# smoothieboard_daugterboard_Plasma.net
KiCad netlist of a schematic drawn in EAGLE
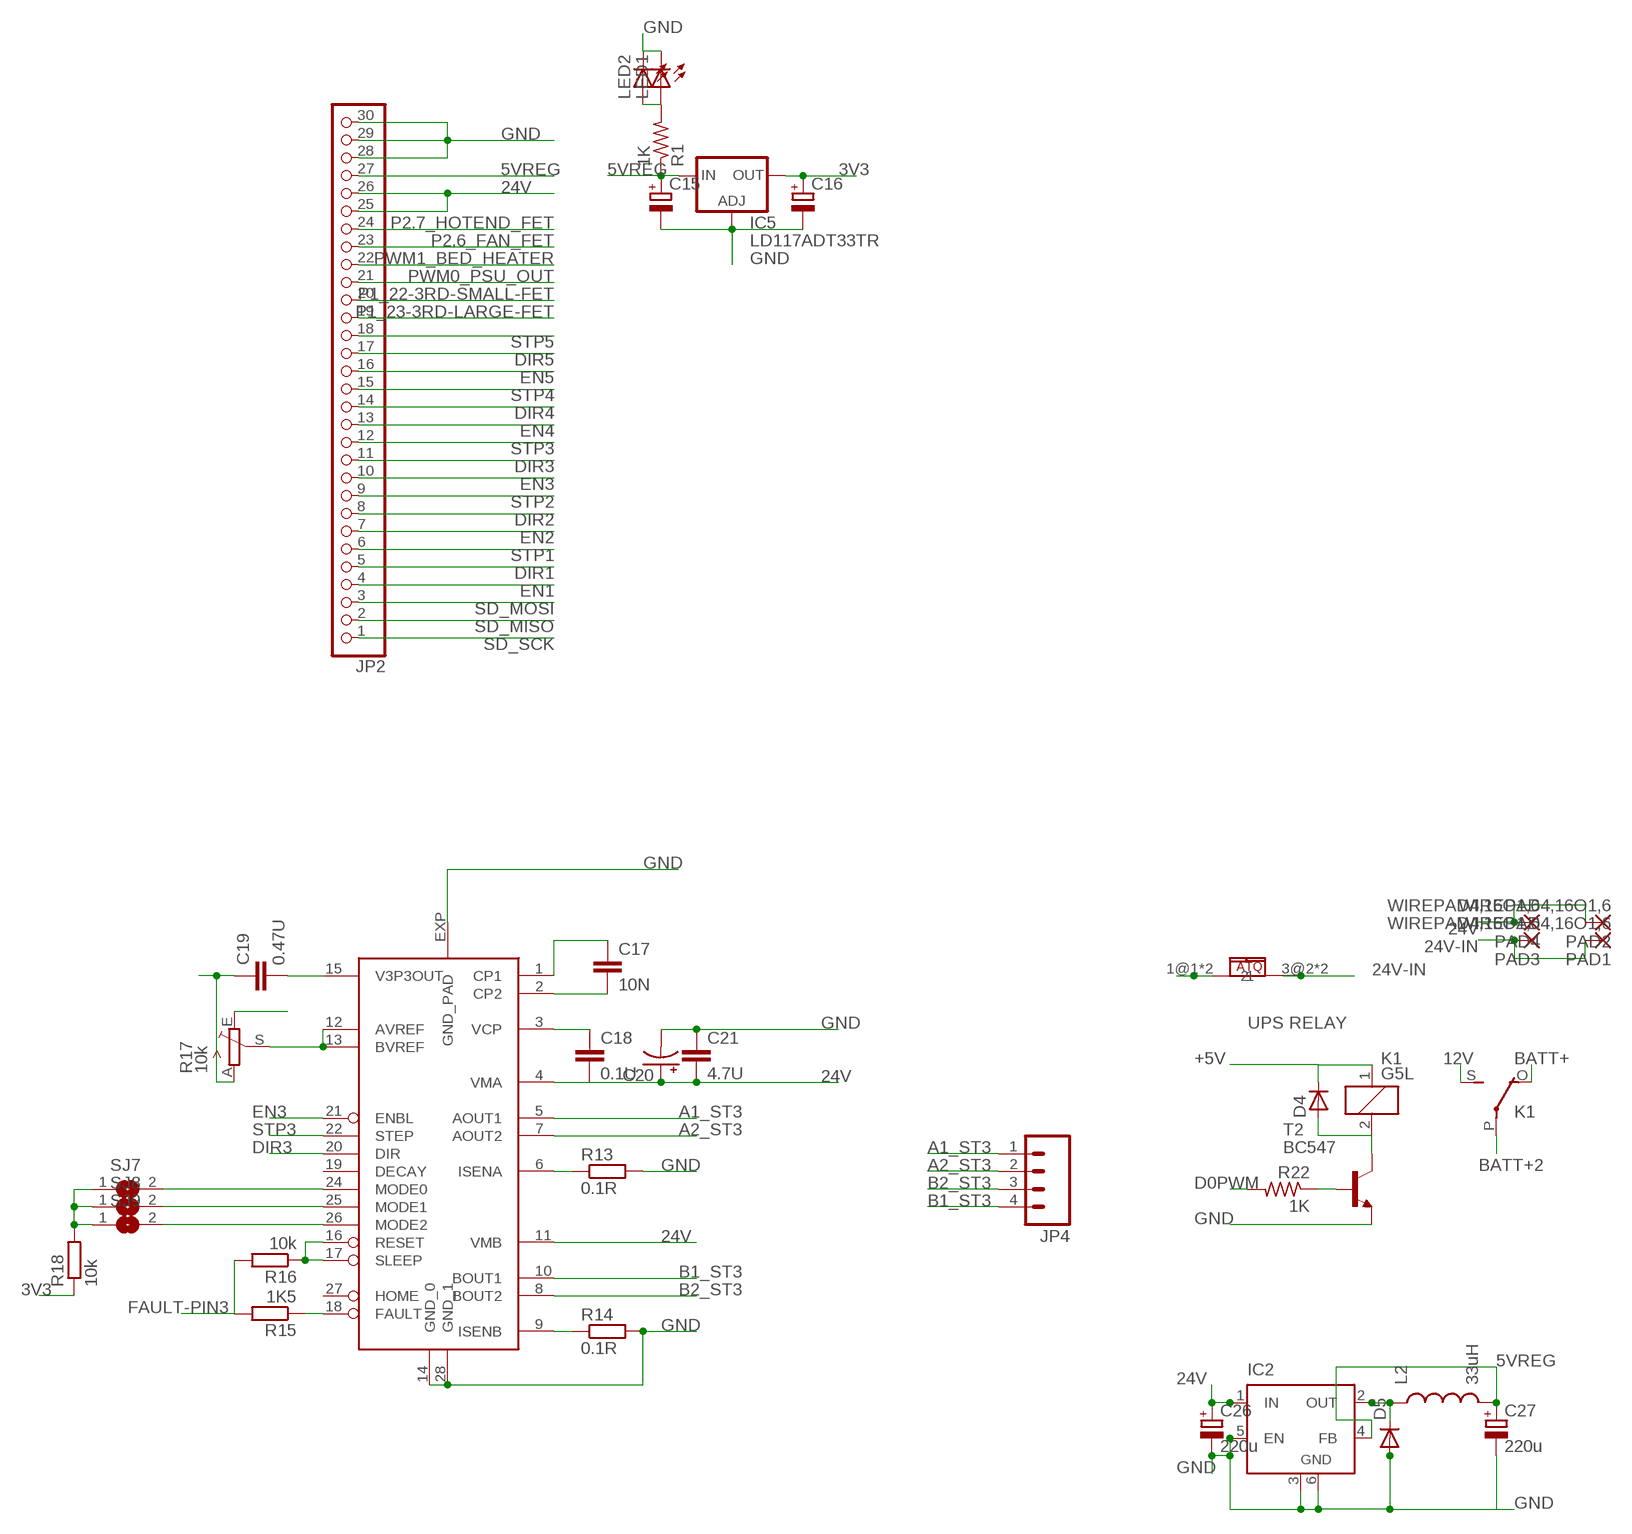
[diagram p0: schematic, sheet 1]

(export (version "E")
  (design (tool "Eeschema 10.0.6"))
  (components
    (comp (ref "C15")
      (value "CPOL-EUB/3528-21R")
      (footprint "eagle-import:B_3528-21R")
      (libsource (lib "eagle-import") (part "CPOL-EUB/3528-21R"))
    )
    (comp (ref "C16")
      (value "CPOL-EUB/3528-21R")
      (footprint "eagle-import:B_3528-21R")
      (libsource (lib "eagle-import") (part "CPOL-EUB/3528-21R"))
    )
    (comp (ref "C17")
      (value "10N")
      (footprint "eagle-import:1206")
      (libsource (lib "eagle-import") (part "CAP1206"))
    )
    (comp (ref "C18")
      (value "0.1U")
      (footprint "eagle-import:1206")
      (libsource (lib "eagle-import") (part "CAP1206"))
    )
    (comp (ref "C19")
      (value "0.47U")
      (footprint "eagle-import:0805")
      (libsource (lib "eagle-import") (part "CAP0805"))
    )
    (comp (ref "C20")
      (value "CPOL-USE2.5-7")
      (footprint "eagle-import:E2,5-7")
      (libsource (lib "eagle-import") (part "CPOL-USE2.5-7"))
    )
    (comp (ref "C21")
      (value "4.7U")
      (footprint "eagle-import:1206")
      (libsource (lib "eagle-import") (part "CAP1206"))
    )
    (comp (ref "C26")
      (value "220u")
      (footprint "eagle-import:PANASONIC_E")
      (libsource (lib "eagle-import") (part "CPOL-EUE"))
    )
    (comp (ref "C27")
      (value "220u")
      (footprint "eagle-import:PANASONIC_E")
      (libsource (lib "eagle-import") (part "CPOL-EUE"))
    )
    (comp (ref "D4")
      (value "D-MLL-41")
      (footprint "eagle-import:MELF-MLL41")
      (libsource (lib "eagle-import") (part "D-MLL-41"))
    )
    (comp (ref "D5")
      (value "DIODE-DO-214AC")
      (footprint "eagle-import:DO-214AC")
      (libsource (lib "eagle-import") (part "DIODE-DO-214AC"))
    )
    (comp (ref "IC2")
      (value "LM2596S")
      (footprint "eagle-import:TO263-5")
      (libsource (lib "eagle-import") (part "LM2596S"))
    )
    (comp (ref "IC5")
      (value "LD117ADT33TR")
      (footprint "eagle-import:DPACK")
      (libsource (lib "eagle-import") (part "LD117A?DT33TR"))
    )
    (comp (ref "JP2")
      (value "PINHD-1X30")
      (footprint "eagle-import:1X30")
      (libsource (lib "eagle-import") (part "PINHD-1X30"))
    )
    (comp (ref "JP4")
      (value "M04SCREW")
      (footprint "eagle-import:SCREWTERMINAL-3.5MM-4")
      (libsource (lib "eagle-import") (part "M04SCREW"))
    )
    (comp (ref "K1")
      (value "G5L")
      (footprint "eagle-import:G5LE")
      (libsource (lib "eagle-import") (part "G5L"))
    )
    (comp (ref "L2")
      (value "33uH")
      (footprint "eagle-import:CDRH125")
      (libsource (lib "eagle-import") (part "INDUCTORPWR"))
    )
    (comp (ref "LED1")
      (value "LEDCHIPLED_1206")
      (footprint "eagle-import:CHIPLED_1206")
      (libsource (lib "eagle-import") (part "LEDCHIPLED_1206"))
    )
    (comp (ref "LED2")
      (value "LED3MM")
      (footprint "eagle-import:LED3MM")
      (libsource (lib "eagle-import") (part "LED3MM"))
    )
    (comp (ref "PAD1")
      (value "WIREPAD4,16O1,6")
      (footprint "eagle-import:4,16O1,6")
      (libsource (lib "eagle-import") (part "WIREPAD4,16O1,6"))
    )
    (comp (ref "PAD2")
      (value "WIREPAD4,16O1,6")
      (footprint "eagle-import:4,16O1,6")
      (libsource (lib "eagle-import") (part "WIREPAD4,16O1,6"))
    )
    (comp (ref "PAD3")
      (value "WIREPAD4,16O1,6")
      (footprint "eagle-import:4,16O1,6")
      (libsource (lib "eagle-import") (part "WIREPAD4,16O1,6"))
    )
    (comp (ref "PAD4")
      (value "WIREPAD4,16O1,6")
      (footprint "eagle-import:4,16O1,6")
      (libsource (lib "eagle-import") (part "WIREPAD4,16O1,6"))
    )
    (comp (ref "R1")
      (value "1K")
      (footprint "eagle-import:M1206")
      (libsource (lib "eagle-import") (part "R-US_M1206"))
    )
    (comp (ref "R13")
      (value "0.1R")
      (footprint "eagle-import:R1206")
      (libsource (lib "eagle-import") (part "R-EU_R1206"))
    )
    (comp (ref "R14")
      (value "0.1R")
      (footprint "eagle-import:R1206")
      (libsource (lib "eagle-import") (part "R-EU_R1206"))
    )
    (comp (ref "R15")
      (value "1K5")
      (footprint "eagle-import:R0805")
      (libsource (lib "eagle-import") (part "R-EU_R0805"))
    )
    (comp (ref "R16")
      (value "10k")
      (footprint "eagle-import:R0805")
      (libsource (lib "eagle-import") (part "R-EU_R0805"))
    )
    (comp (ref "R17")
      (value "10k")
      (footprint "eagle-import:S64W")
      (libsource (lib "eagle-import") (part "TRIM_EU-S64W"))
    )
    (comp (ref "R18")
      (value "10k")
      (footprint "eagle-import:R1206")
      (libsource (lib "eagle-import") (part "R-EU_R1206"))
    )
    (comp (ref "R22")
      (value "1K")
      (footprint "eagle-import:M1206")
      (libsource (lib "eagle-import") (part "R-US_M1206"))
    )
    (comp (ref "SJ7") (value "SJ") (footprint "eagle-import:SJ") (libsource (lib "eagle-import") (part "SJ")))
    (comp (ref "SJ8") (value "SJ") (footprint "eagle-import:SJ") (libsource (lib "eagle-import") (part "SJ")))
    (comp (ref "SJ9") (value "SJ") (footprint "eagle-import:SJ") (libsource (lib "eagle-import") (part "SJ")))
    (comp (ref "T2")
      (value "BC547")
      (footprint "eagle-import:TO92")
      (libsource (lib "eagle-import") (part "BC547"))
    )
    (comp (ref "U$3")
      (value "DRV8825PWP")
      (footprint "eagle-import:TSSOP-28")
      (libsource (lib "eagle-import") (part "DRV8825PWP"))
    )
    (comp (ref "U$7")
      (value "CQ-121")
      (footprint "eagle-import:CQ121")
      (libsource (lib "eagle-import") (part "CQ-121"))
    )
  )
  (nets
    (net (code "1") (name "+5V") (class "Default")
      (node (ref "D4") (pin "1") (pinfunction "C_1") (pintype "passive"))
      (node (ref "K1") (pin "1") (pinfunction "1_1") (pintype "passive"))
    )
    (net (code "2") (name "3V3") (class "Default")
      (node (ref "C16") (pin "+") (pinfunction "+_+") (pintype "passive"))
      (node (ref "IC5") (pin "4") (pinfunction "OUT_4") (pintype "passive"))
      (node (ref "R17") (pin "E") (pinfunction "E_E") (pintype "passive"))
      (node (ref "R18") (pin "1") (pinfunction "1_1") (pintype "passive"))
    )
    (net (code "3") (name "5VREG") (class "Default")
      (node (ref "C15") (pin "+") (pinfunction "+_+") (pintype "passive"))
      (node (ref "C27") (pin "+") (pinfunction "+_+") (pintype "passive"))
      (node (ref "IC2") (pin "4") (pinfunction "FB_4") (pintype "input"))
      (node (ref "IC5") (pin "3") (pinfunction "IN_3") (pintype "input"))
      (node (ref "JP2") (pin "27") (pinfunction "27_27") (pintype "passive"))
      (node (ref "L2") (pin "2") (pinfunction "2_2") (pintype "passive"))
      (node (ref "R1") (pin "1") (pinfunction "1_1") (pintype "passive"))
    )
    (net (code "4") (name "12V") (class "Default")
      (node (ref "K1") (pin "S") (pinfunction "S_S") (pintype "passive"))
    )
    (net (code "5") (name "24V") (class "Default")
      (node (ref "C18") (pin "2") (pinfunction "2_2") (pintype "passive"))
      (node (ref "C20") (pin "+") (pinfunction "+_+") (pintype "passive"))
      (node (ref "C21") (pin "2") (pinfunction "2_2") (pintype "passive"))
      (node (ref "C26") (pin "+") (pinfunction "+_+") (pintype "passive"))
      (node (ref "IC2") (pin "1") (pinfunction "IN_1") (pintype "input"))
      (node (ref "JP2") (pin "25") (pinfunction "25_25") (pintype "passive"))
      (node (ref "JP2") (pin "26") (pinfunction "26_26") (pintype "passive"))
      (node (ref "PAD2") (pin "1") (pinfunction "P_1") (pintype "passive"))
      (node (ref "PAD4") (pin "1") (pinfunction "P_1") (pintype "passive"))
      (node (ref "U$3") (pin "11") (pinfunction "VMB_11") (pintype "power_in"))
      (node (ref "U$3") (pin "4") (pinfunction "VMA_4") (pintype "power_in"))
    )
    (net (code "6") (name "24V-IN") (class "Default")
      (node (ref "PAD1") (pin "1") (pinfunction "P_1") (pintype "passive"))
      (node (ref "PAD3") (pin "1") (pinfunction "P_1") (pintype "passive"))
      (node (ref "U$7") (pin "3@2") (pinfunction "2_3@2") (pintype "bidirectional"))
      (node (ref "U$7") (pin "4@2") (pinfunction "2_4@2") (pintype "bidirectional"))
    )
    (net (code "7") (name "A1_ST3") (class "Default")
      (node (ref "JP4") (pin "1") (pinfunction "1_1") (pintype "passive"))
      (node (ref "U$3") (pin "5") (pinfunction "AOUT1_5") (pintype "output"))
    )
    (net (code "8") (name "A2_ST3") (class "Default")
      (node (ref "JP4") (pin "2") (pinfunction "2_2") (pintype "passive"))
      (node (ref "U$3") (pin "7") (pinfunction "AOUT2_7") (pintype "output"))
    )
    (net (code "9") (name "B1_ST3") (class "Default")
      (node (ref "JP4") (pin "4") (pinfunction "4_4") (pintype "passive"))
      (node (ref "U$3") (pin "10") (pinfunction "BOUT1_10") (pintype "output"))
    )
    (net (code "10") (name "B2_ST3") (class "Default")
      (node (ref "JP4") (pin "3") (pinfunction "3_3") (pintype "passive"))
      (node (ref "U$3") (pin "8") (pinfunction "BOUT2_8") (pintype "output"))
    )
    (net (code "11") (name "BATT+") (class "Default")
      (node (ref "K1") (pin "O") (pinfunction "O_O") (pintype "passive"))
    )
    (net (code "12") (name "BATT+2") (class "Default")
      (node (ref "K1") (pin "P") (pinfunction "P_P") (pintype "passive"))
    )
    (net (code "13") (name "D0PWM") (class "Default")
      (node (ref "R22") (pin "2") (pinfunction "2_2") (pintype "passive"))
    )
    (net (code "14") (name "DIR1") (class "Default")
      (node (ref "JP2") (pin "5") (pinfunction "5_5") (pintype "passive"))
    )
    (net (code "15") (name "DIR2") (class "Default")
      (node (ref "JP2") (pin "8") (pinfunction "8_8") (pintype "passive"))
    )
    (net (code "16") (name "DIR3") (class "Default")
      (node (ref "JP2") (pin "11") (pinfunction "11_11") (pintype "passive"))
      (node (ref "U$3") (pin "20") (pinfunction "DIR_20") (pintype "input"))
    )
    (net (code "17") (name "DIR4") (class "Default")
      (node (ref "JP2") (pin "14") (pinfunction "14_14") (pintype "passive"))
    )
    (net (code "18") (name "DIR5") (class "Default")
      (node (ref "JP2") (pin "17") (pinfunction "17_17") (pintype "passive"))
    )
    (net (code "19") (name "EN1") (class "Default")
      (node (ref "JP2") (pin "4") (pinfunction "4_4") (pintype "passive"))
    )
    (net (code "20") (name "EN2") (class "Default")
      (node (ref "JP2") (pin "7") (pinfunction "7_7") (pintype "passive"))
    )
    (net (code "21") (name "EN3") (class "Default")
      (node (ref "JP2") (pin "10") (pinfunction "10_10") (pintype "passive"))
      (node (ref "U$3") (pin "21") (pinfunction "ENBL_21") (pintype "input"))
    )
    (net (code "22") (name "EN4") (class "Default")
      (node (ref "JP2") (pin "13") (pinfunction "13_13") (pintype "passive"))
    )
    (net (code "23") (name "EN5") (class "Default")
      (node (ref "JP2") (pin "16") (pinfunction "16_16") (pintype "passive"))
    )
    (net (code "24") (name "FAULT-PIN3") (class "Default")
      (node (ref "R15") (pin "2") (pinfunction "2_2") (pintype "passive"))
      (node (ref "R16") (pin "2") (pinfunction "2_2") (pintype "passive"))
    )
    (net (code "25") (name "GND") (class "Default")
      (node (ref "C15") (pin "-") (pinfunction "-_-") (pintype "passive"))
      (node (ref "C16") (pin "-") (pinfunction "-_-") (pintype "passive"))
      (node (ref "C19") (pin "1") (pinfunction "1_1") (pintype "passive"))
      (node (ref "C20") (pin "-") (pinfunction "-_-") (pintype "passive"))
      (node (ref "C21") (pin "1") (pinfunction "1_1") (pintype "passive"))
      (node (ref "C26") (pin "-") (pinfunction "-_-") (pintype "passive"))
      (node (ref "C27") (pin "-") (pinfunction "-_-") (pintype "passive"))
      (node (ref "D5") (pin "2") (pinfunction "A_2") (pintype "passive"))
      (node (ref "IC2") (pin "3") (pinfunction "GND_3") (pintype "power_in"))
      (node (ref "IC2") (pin "5") (pinfunction "EN_5") (pintype "input"))
      (node (ref "IC2") (pin "6") (pinfunction "GND_6") (pintype "power_in"))
      (node (ref "IC5") (pin "1") (pinfunction "ADJ_1") (pintype "input"))
      (node (ref "JP2") (pin "28") (pinfunction "28_28") (pintype "passive"))
      (node (ref "JP2") (pin "29") (pinfunction "29_29") (pintype "passive"))
      (node (ref "JP2") (pin "30") (pinfunction "30_30") (pintype "passive"))
      (node (ref "LED1") (pin "C") (pinfunction "C_C") (pintype "passive"))
      (node (ref "LED2") (pin "K") (pinfunction "C_K") (pintype "passive"))
      (node (ref "R13") (pin "2") (pinfunction "2_2") (pintype "passive"))
      (node (ref "R14") (pin "2") (pinfunction "2_2") (pintype "passive"))
      (node (ref "R17") (pin "A") (pinfunction "A_A") (pintype "passive"))
      (node (ref "T2") (pin "1") (pinfunction "E_1") (pintype "passive"))
      (node (ref "U$3") (pin "14") (pinfunction "GND_0_14") (pintype "power_in"))
      (node (ref "U$3") (pin "28") (pinfunction "GND_1_28") (pintype "power_in"))
      (node (ref "U$3") (pin "EXP") (pinfunction "GND_PAD_EXP") (pintype "power_in"))
    )
    (net (code "26") (name "MSPULLUP2") (class "Default")
      (node (ref "R18") (pin "2") (pinfunction "2_2") (pintype "passive"))
      (node (ref "SJ7") (pin "1") (pinfunction "1_1") (pintype "passive"))
      (node (ref "SJ7") (pin "2") (pinfunction "2_2") (pintype "passive"))
      (node (ref "SJ8") (pin "1") (pinfunction "1_1") (pintype "passive"))
      (node (ref "SJ8") (pin "2") (pinfunction "2_2") (pintype "passive"))
      (node (ref "SJ9") (pin "1") (pinfunction "1_1") (pintype "passive"))
      (node (ref "SJ9") (pin "2") (pinfunction "2_2") (pintype "passive"))
      (node (ref "U$3") (pin "24") (pinfunction "MODE0_24") (pintype "input"))
      (node (ref "U$3") (pin "25") (pinfunction "MODE1_25") (pintype "input"))
      (node (ref "U$3") (pin "26") (pinfunction "MODE2_26") (pintype "input"))
    )
    (net (code "27") (name "Net-(D4-A)") (class "Default")
      (node (ref "D4") (pin "2") (pinfunction "A_2") (pintype "passive"))
      (node (ref "K1") (pin "2") (pinfunction "2_2") (pintype "passive"))
      (node (ref "T2") (pin "3") (pinfunction "C_3") (pintype "passive"))
    )
    (net (code "28") (name "Net-(D5-C)") (class "Default")
      (node (ref "D5") (pin "1") (pinfunction "C_1") (pintype "passive"))
      (node (ref "IC2") (pin "2") (pinfunction "OUT_2") (pintype "output"))
      (node (ref "L2") (pin "1") (pinfunction "1_1") (pintype "passive"))
    )
    (net (code "29") (name "Net-(LED1-PadA)") (class "Default")
      (node (ref "LED1") (pin "A") (pinfunction "A_A") (pintype "passive"))
      (node (ref "LED2") (pin "A") (pinfunction "A_A") (pintype "passive"))
      (node (ref "R1") (pin "2") (pinfunction "2_2") (pintype "passive"))
    )
    (net (code "30") (name "Net-(T2-B)") (class "Default")
      (node (ref "R22") (pin "1") (pinfunction "1_1") (pintype "passive"))
      (node (ref "T2") (pin "2") (pinfunction "B_2") (pintype "passive"))
    )
    (net (code "31") (name "Net-(U$3-AVREF)") (class "Default")
      (node (ref "R17") (pin "S") (pinfunction "S_S") (pintype "passive"))
      (node (ref "U$3") (pin "12") (pinfunction "AVREF_12") (pintype "input"))
      (node (ref "U$3") (pin "13") (pinfunction "BVREF_13") (pintype "input"))
    )
    (net (code "32") (name "Net-(U$3-CP1)") (class "Default")
      (node (ref "C17") (pin "1") (pinfunction "1_1") (pintype "passive"))
      (node (ref "U$3") (pin "1") (pinfunction "CP1_1") (pintype "bidirectional"))
    )
    (net (code "33") (name "Net-(U$3-CP2)") (class "Default")
      (node (ref "C17") (pin "2") (pinfunction "2_2") (pintype "passive"))
      (node (ref "U$3") (pin "2") (pinfunction "CP2_2") (pintype "bidirectional"))
    )
    (net (code "34") (name "Net-(U$3-FAULT)") (class "Default")
      (node (ref "R15") (pin "1") (pinfunction "1_1") (pintype "passive"))
      (node (ref "U$3") (pin "18") (pinfunction "FAULT_18") (pintype "output"))
    )
    (net (code "35") (name "Net-(U$3-ISENA)") (class "Default")
      (node (ref "R13") (pin "1") (pinfunction "1_1") (pintype "passive"))
      (node (ref "U$3") (pin "6") (pinfunction "ISENA_6") (pintype "output"))
    )
    (net (code "36") (name "Net-(U$3-ISENB)") (class "Default")
      (node (ref "R14") (pin "1") (pinfunction "1_1") (pintype "passive"))
      (node (ref "U$3") (pin "9") (pinfunction "ISENB_9") (pintype "output"))
    )
    (net (code "37") (name "Net-(U$3-RESET)") (class "Default")
      (node (ref "R16") (pin "1") (pinfunction "1_1") (pintype "passive"))
      (node (ref "U$3") (pin "16") (pinfunction "RESET_16") (pintype "input"))
      (node (ref "U$3") (pin "17") (pinfunction "SLEEP_17") (pintype "input"))
    )
    (net (code "38") (name "Net-(U$3-V3P3OUT)") (class "Default")
      (node (ref "C19") (pin "2") (pinfunction "2_2") (pintype "passive"))
      (node (ref "U$3") (pin "15") (pinfunction "V3P3OUT_15") (pintype "output"))
    )
    (net (code "39") (name "Net-(U$3-VCP)") (class "Default")
      (node (ref "C18") (pin "1") (pinfunction "1_1") (pintype "passive"))
      (node (ref "U$3") (pin "3") (pinfunction "VCP_3") (pintype "bidirectional"))
    )
    (net (code "40") (name "Net-(U$7-1-Pad1@1)") (class "Default")
      (node (ref "U$7") (pin "1@1") (pinfunction "1_1@1") (pintype "bidirectional"))
      (node (ref "U$7") (pin "2@1") (pinfunction "1_2@1") (pintype "bidirectional"))
    )
    (net (code "41") (name "P1_22-3RD-SMALL-FET") (class "Default")
      (node (ref "JP2") (pin "20") (pinfunction "20_20") (pintype "passive"))
    )
    (net (code "42") (name "P1_23-3RD-LARGE-FET") (class "Default")
      (node (ref "JP2") (pin "19") (pinfunction "19_19") (pintype "passive"))
    )
    (net (code "43") (name "P2.6_FAN_FET") (class "Default")
      (node (ref "JP2") (pin "23") (pinfunction "23_23") (pintype "passive"))
    )
    (net (code "44") (name "P2.7_HOTEND_FET") (class "Default")
      (node (ref "JP2") (pin "24") (pinfunction "24_24") (pintype "passive"))
    )
    (net (code "45") (name "PWM0_PSU_OUT") (class "Default")
      (node (ref "JP2") (pin "21") (pinfunction "21_21") (pintype "passive"))
    )
    (net (code "46") (name "PWM1_BED_HEATER") (class "Default")
      (node (ref "JP2") (pin "22") (pinfunction "22_22") (pintype "passive"))
    )
    (net (code "47") (name "SD_MISO") (class "Default")
      (node (ref "JP2") (pin "2") (pinfunction "2_2") (pintype "passive"))
    )
    (net (code "48") (name "SD_MOSI") (class "Default")
      (node (ref "JP2") (pin "3") (pinfunction "3_3") (pintype "passive"))
    )
    (net (code "49") (name "SD_SCK") (class "Default")
      (node (ref "JP2") (pin "1") (pinfunction "1_1") (pintype "passive"))
    )
    (net (code "50") (name "STP1") (class "Default")
      (node (ref "JP2") (pin "6") (pinfunction "6_6") (pintype "passive"))
    )
    (net (code "51") (name "STP2") (class "Default")
      (node (ref "JP2") (pin "9") (pinfunction "9_9") (pintype "passive"))
    )
    (net (code "52") (name "STP3") (class "Default")
      (node (ref "JP2") (pin "12") (pinfunction "12_12") (pintype "passive"))
      (node (ref "U$3") (pin "22") (pinfunction "STEP_22") (pintype "input"))
    )
    (net (code "53") (name "STP4") (class "Default")
      (node (ref "JP2") (pin "15") (pinfunction "15_15") (pintype "passive"))
    )
    (net (code "54") (name "STP5") (class "Default")
      (node (ref "JP2") (pin "18") (pinfunction "18_18") (pintype "passive"))
    )
    (net (code "55") (name "unconnected-(U$3-DECAY-Pad19)") (class "Default")
      (node (ref "U$3") (pin "19") (pinfunction "DECAY_19") (pintype "input"))
    )
    (net (code "56") (name "unconnected-(U$3-HOME-Pad27)") (class "Default")
      (node (ref "U$3") (pin "27") (pinfunction "HOME_27") (pintype "output"))
    )
  )
)
